# Microcontroller_board_Photodiode_plate.net
KiCad netlist of a schematic drawn in EasyEDA
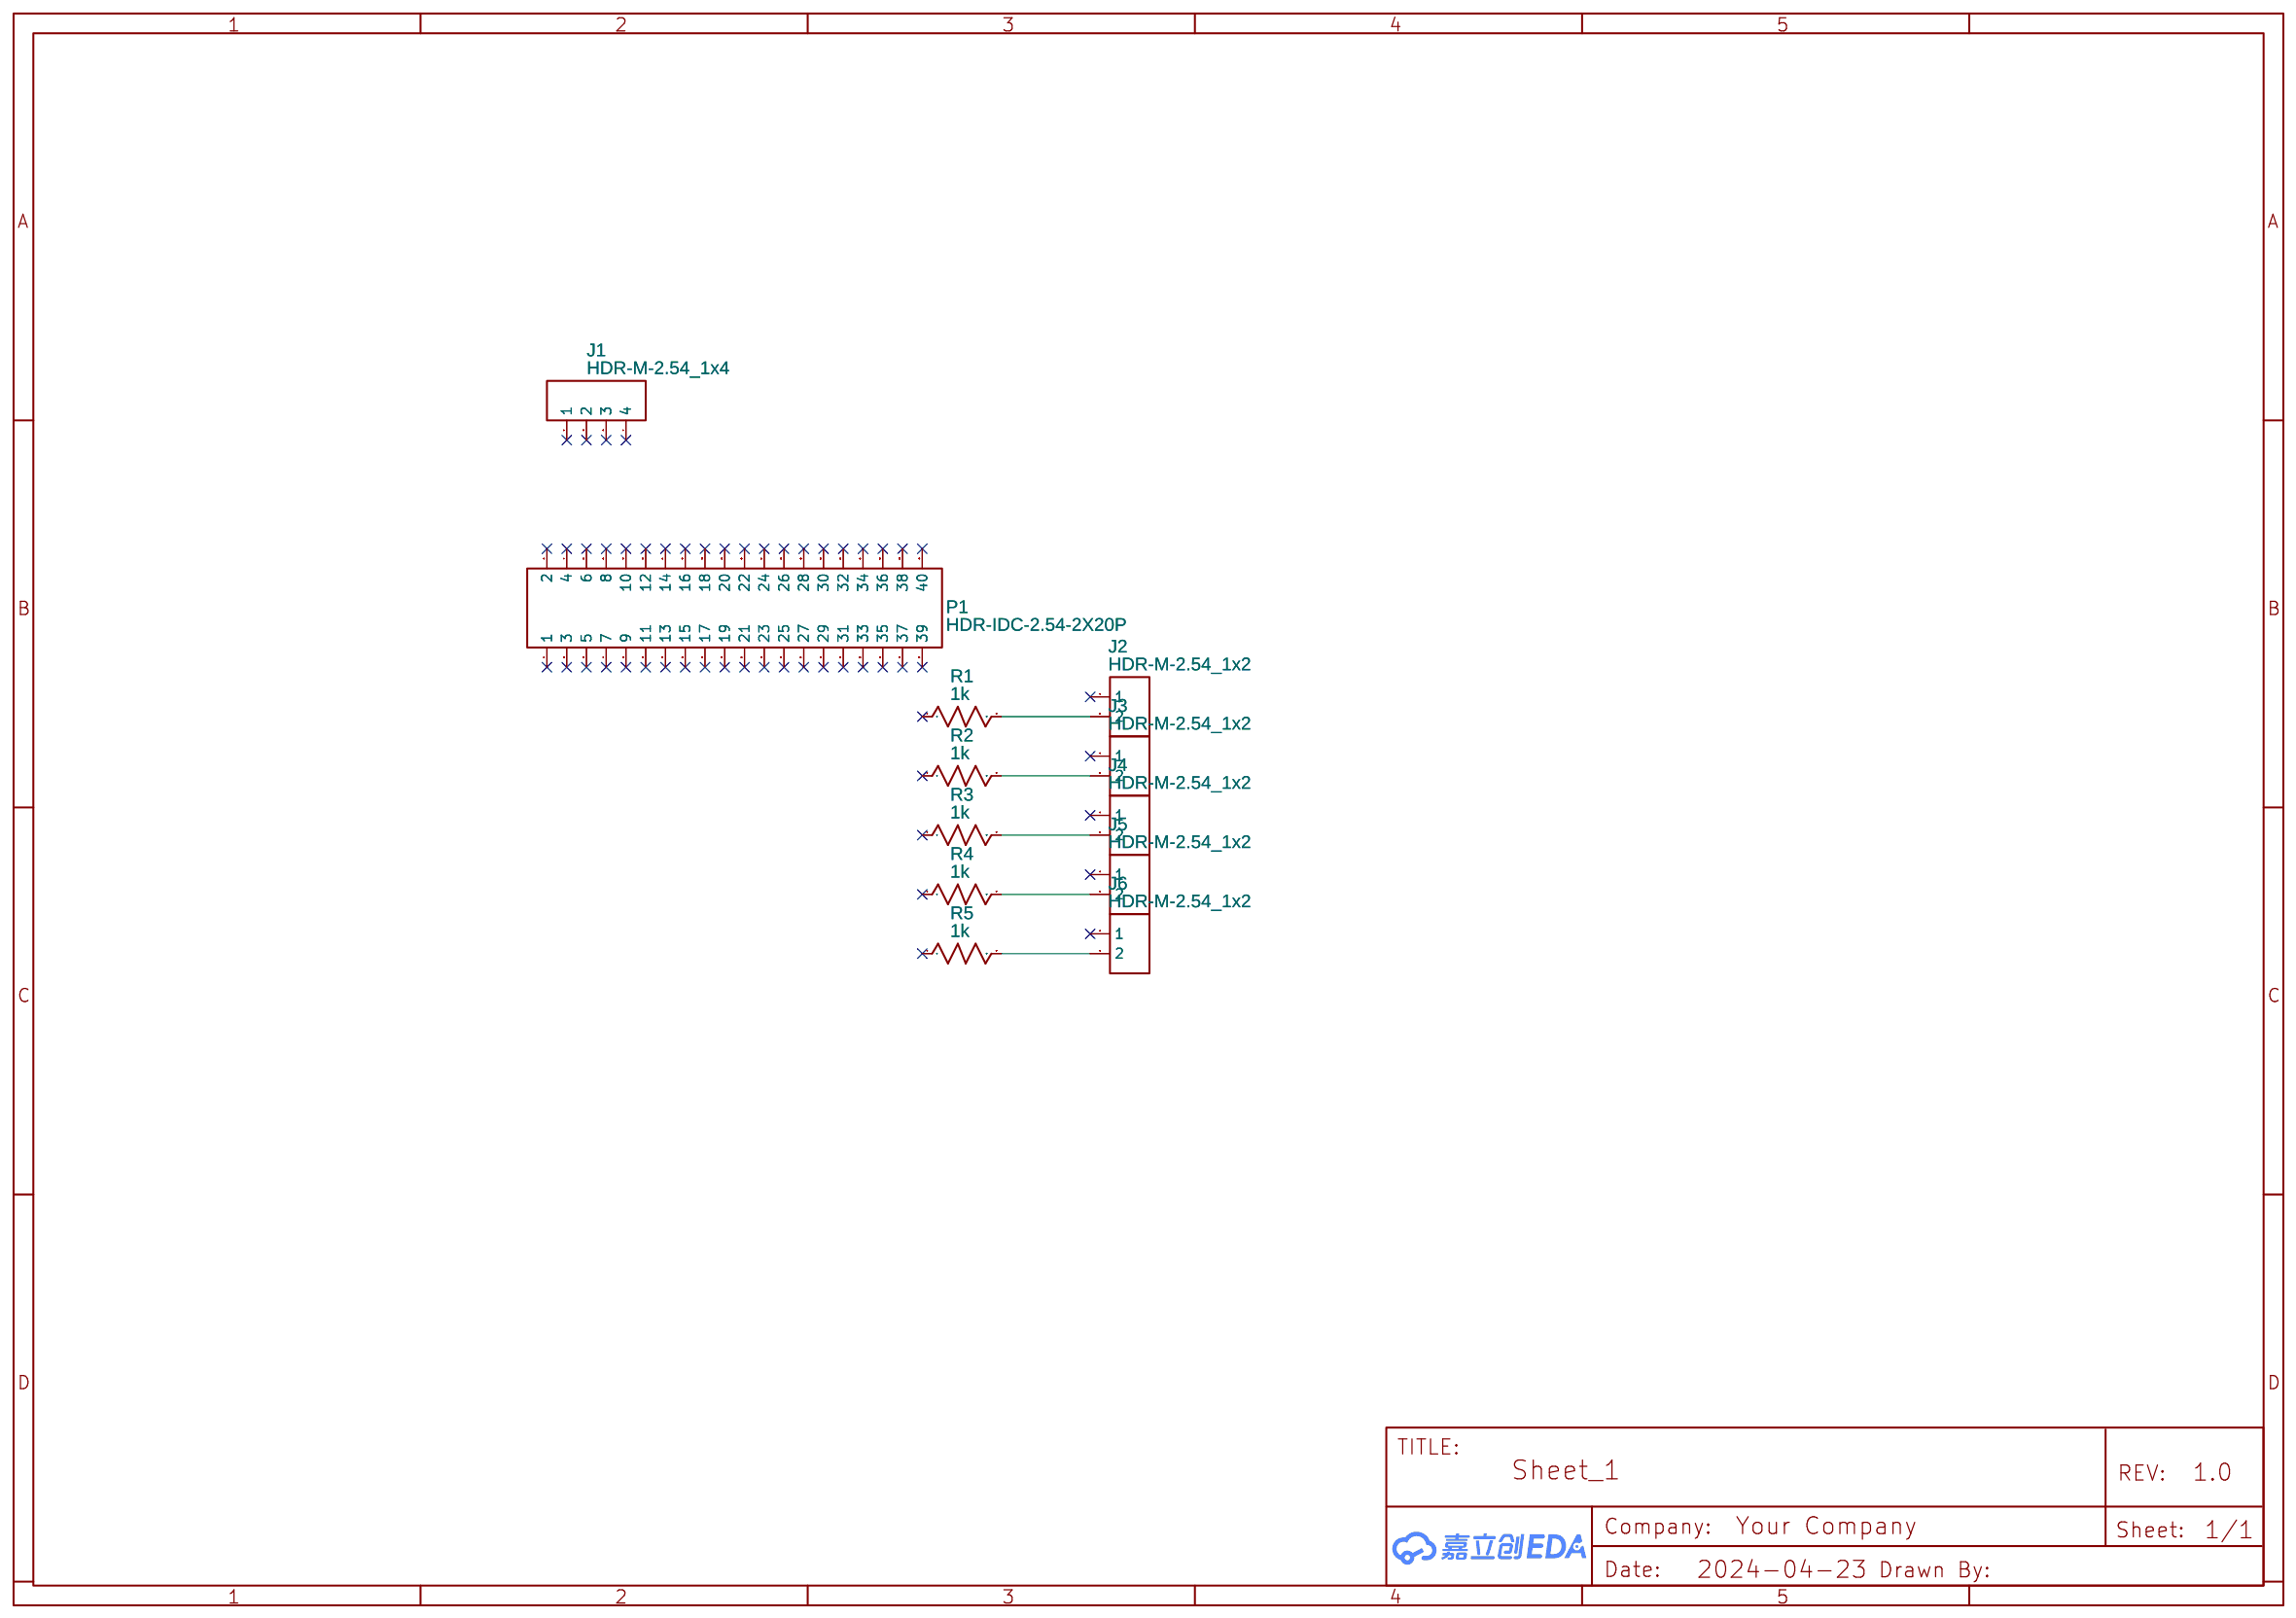
[diagram p0: schematic sheet]

(export (version "E")
  (design (tool "Eeschema 10.0.6"))
  (components
    (comp (ref "J1")
      (value "HDR-M-2.54_1x4")
      (fields (field (name "BOM_Supplier Part") "C124378"))
      (libsource (lib "") (part "HDR-M-2.54_1x4"))
    )
    (comp (ref "J2")
      (value "HDR-M-2.54_1x2")
      (fields (field (name "BOM_Supplier Part") "C124375"))
      (libsource (lib "") (part "HDR-M-2.54_1x2"))
    )
    (comp (ref "J3")
      (value "HDR-M-2.54_1x2")
      (fields (field (name "BOM_Supplier Part") "C124375"))
      (libsource (lib "") (part "HDR-M-2.54_1x2"))
    )
    (comp (ref "J4")
      (value "HDR-M-2.54_1x2")
      (fields (field (name "BOM_Supplier Part") "C124375"))
      (libsource (lib "") (part "HDR-M-2.54_1x2"))
    )
    (comp (ref "J5")
      (value "HDR-M-2.54_1x2")
      (fields (field (name "BOM_Supplier Part") "C124375"))
      (libsource (lib "") (part "HDR-M-2.54_1x2"))
    )
    (comp (ref "J6")
      (value "HDR-M-2.54_1x2")
      (fields (field (name "BOM_Supplier Part") "C124375"))
      (libsource (lib "") (part "HDR-M-2.54_1x2"))
    )
    (comp (ref "P1")
      (value "HDR-IDC-2.54-2X20P")
      (fields
        (field (name "BOM_Manufacturer Part") "IDC Box 2X20 2.54MM")
        (field (name "BOM_Supplier Part") "C9138")
      )
      (libsource (lib "") (part "HDR-IDC-2.54-2X20P"))
    )
    (comp (ref "R1") (value "1k") (libsource (lib "") (part "R_0603_US")))
    (comp (ref "R2") (value "1k") (libsource (lib "") (part "R_0603_US")))
    (comp (ref "R3") (value "1k") (libsource (lib "") (part "R_0603_US")))
    (comp (ref "R4") (value "1k") (libsource (lib "") (part "R_0603_US")))
    (comp (ref "R5") (value "1k") (libsource (lib "") (part "R_0603_US")))
  )
  (nets
    (net (code "1") (name "Net-(J2-Pad2)") (class "Default")
      (node (ref "J2") (pin "2") (pinfunction "2_2") (pintype "unspecified"))
      (node (ref "R1") (pin "2") (pinfunction "2_2") (pintype "unspecified"))
    )
    (net (code "2") (name "Net-(J3-Pad2)") (class "Default")
      (node (ref "J3") (pin "2") (pinfunction "2_2") (pintype "unspecified"))
      (node (ref "R2") (pin "2") (pinfunction "2_2") (pintype "unspecified"))
    )
    (net (code "3") (name "Net-(J4-Pad2)") (class "Default")
      (node (ref "J4") (pin "2") (pinfunction "2_2") (pintype "unspecified"))
      (node (ref "R3") (pin "2") (pinfunction "2_2") (pintype "unspecified"))
    )
    (net (code "4") (name "Net-(J5-Pad2)") (class "Default")
      (node (ref "J5") (pin "2") (pinfunction "2_2") (pintype "unspecified"))
      (node (ref "R4") (pin "2") (pinfunction "2_2") (pintype "unspecified"))
    )
    (net (code "5") (name "Net-(J6-Pad2)") (class "Default")
      (node (ref "J6") (pin "2") (pinfunction "2_2") (pintype "unspecified"))
      (node (ref "R5") (pin "2") (pinfunction "2_2") (pintype "unspecified"))
    )
    (net (code "6") (name "unconnected-(J1-Pad1)") (class "Default")
      (node (ref "J1") (pin "1") (pinfunction "1_1") (pintype "unspecified+no_connect"))
    )
    (net (code "7") (name "unconnected-(J1-Pad2)") (class "Default")
      (node (ref "J1") (pin "2") (pinfunction "2_2") (pintype "unspecified+no_connect"))
    )
    (net (code "8") (name "unconnected-(J1-Pad3)") (class "Default")
      (node (ref "J1") (pin "3") (pinfunction "3_3") (pintype "unspecified+no_connect"))
    )
    (net (code "9") (name "unconnected-(J1-Pad4)") (class "Default")
      (node (ref "J1") (pin "4") (pinfunction "4_4") (pintype "unspecified+no_connect"))
    )
    (net (code "10") (name "unconnected-(J2-Pad1)") (class "Default")
      (node (ref "J2") (pin "1") (pinfunction "1_1") (pintype "unspecified+no_connect"))
    )
    (net (code "11") (name "unconnected-(J3-Pad1)") (class "Default")
      (node (ref "J3") (pin "1") (pinfunction "1_1") (pintype "unspecified+no_connect"))
    )
    (net (code "12") (name "unconnected-(J4-Pad1)") (class "Default")
      (node (ref "J4") (pin "1") (pinfunction "1_1") (pintype "unspecified+no_connect"))
    )
    (net (code "13") (name "unconnected-(J5-Pad1)") (class "Default")
      (node (ref "J5") (pin "1") (pinfunction "1_1") (pintype "unspecified+no_connect"))
    )
    (net (code "14") (name "unconnected-(J6-Pad1)") (class "Default")
      (node (ref "J6") (pin "1") (pinfunction "1_1") (pintype "unspecified+no_connect"))
    )
    (net (code "15") (name "unconnected-(P1-Pad1)") (class "Default")
      (node (ref "P1") (pin "1") (pinfunction "1_1") (pintype "unspecified+no_connect"))
    )
    (net (code "16") (name "unconnected-(P1-Pad2)") (class "Default")
      (node (ref "P1") (pin "2") (pinfunction "2_2") (pintype "unspecified+no_connect"))
    )
    (net (code "17") (name "unconnected-(P1-Pad3)") (class "Default")
      (node (ref "P1") (pin "3") (pinfunction "3_3") (pintype "unspecified+no_connect"))
    )
    (net (code "18") (name "unconnected-(P1-Pad4)") (class "Default")
      (node (ref "P1") (pin "4") (pinfunction "4_4") (pintype "unspecified+no_connect"))
    )
    (net (code "19") (name "unconnected-(P1-Pad5)") (class "Default")
      (node (ref "P1") (pin "5") (pinfunction "5_5") (pintype "unspecified+no_connect"))
    )
    (net (code "20") (name "unconnected-(P1-Pad6)") (class "Default")
      (node (ref "P1") (pin "6") (pinfunction "6_6") (pintype "unspecified+no_connect"))
    )
    (net (code "21") (name "unconnected-(P1-Pad7)") (class "Default")
      (node (ref "P1") (pin "7") (pinfunction "7_7") (pintype "unspecified+no_connect"))
    )
    (net (code "22") (name "unconnected-(P1-Pad8)") (class "Default")
      (node (ref "P1") (pin "8") (pinfunction "8_8") (pintype "unspecified+no_connect"))
    )
    (net (code "23") (name "unconnected-(P1-Pad9)") (class "Default")
      (node (ref "P1") (pin "9") (pinfunction "9_9") (pintype "unspecified+no_connect"))
    )
    (net (code "24") (name "unconnected-(P1-Pad10)") (class "Default")
      (node (ref "P1") (pin "10") (pinfunction "10_10") (pintype "unspecified+no_connect"))
    )
    (net (code "25") (name "unconnected-(P1-Pad11)") (class "Default")
      (node (ref "P1") (pin "11") (pinfunction "11_11") (pintype "unspecified+no_connect"))
    )
    (net (code "26") (name "unconnected-(P1-Pad12)") (class "Default")
      (node (ref "P1") (pin "12") (pinfunction "12_12") (pintype "unspecified+no_connect"))
    )
    (net (code "27") (name "unconnected-(P1-Pad13)") (class "Default")
      (node (ref "P1") (pin "13") (pinfunction "13_13") (pintype "unspecified+no_connect"))
    )
    (net (code "28") (name "unconnected-(P1-Pad14)") (class "Default")
      (node (ref "P1") (pin "14") (pinfunction "14_14") (pintype "unspecified+no_connect"))
    )
    (net (code "29") (name "unconnected-(P1-Pad15)") (class "Default")
      (node (ref "P1") (pin "15") (pinfunction "15_15") (pintype "unspecified+no_connect"))
    )
    (net (code "30") (name "unconnected-(P1-Pad16)") (class "Default")
      (node (ref "P1") (pin "16") (pinfunction "16_16") (pintype "unspecified+no_connect"))
    )
    (net (code "31") (name "unconnected-(P1-Pad17)") (class "Default")
      (node (ref "P1") (pin "17") (pinfunction "17_17") (pintype "unspecified+no_connect"))
    )
    (net (code "32") (name "unconnected-(P1-Pad18)") (class "Default")
      (node (ref "P1") (pin "18") (pinfunction "18_18") (pintype "unspecified+no_connect"))
    )
    (net (code "33") (name "unconnected-(P1-Pad19)") (class "Default")
      (node (ref "P1") (pin "19") (pinfunction "19_19") (pintype "unspecified+no_connect"))
    )
    (net (code "34") (name "unconnected-(P1-Pad20)") (class "Default")
      (node (ref "P1") (pin "20") (pinfunction "20_20") (pintype "unspecified+no_connect"))
    )
    (net (code "35") (name "unconnected-(P1-Pad21)") (class "Default")
      (node (ref "P1") (pin "21") (pinfunction "21_21") (pintype "unspecified+no_connect"))
    )
    (net (code "36") (name "unconnected-(P1-Pad22)") (class "Default")
      (node (ref "P1") (pin "22") (pinfunction "22_22") (pintype "unspecified+no_connect"))
    )
    (net (code "37") (name "unconnected-(P1-Pad23)") (class "Default")
      (node (ref "P1") (pin "23") (pinfunction "23_23") (pintype "unspecified+no_connect"))
    )
    (net (code "38") (name "unconnected-(P1-Pad24)") (class "Default")
      (node (ref "P1") (pin "24") (pinfunction "24_24") (pintype "unspecified+no_connect"))
    )
    (net (code "39") (name "unconnected-(P1-Pad25)") (class "Default")
      (node (ref "P1") (pin "25") (pinfunction "25_25") (pintype "unspecified+no_connect"))
    )
    (net (code "40") (name "unconnected-(P1-Pad26)") (class "Default")
      (node (ref "P1") (pin "26") (pinfunction "26_26") (pintype "unspecified+no_connect"))
    )
    (net (code "41") (name "unconnected-(P1-Pad27)") (class "Default")
      (node (ref "P1") (pin "27") (pinfunction "27_27") (pintype "unspecified+no_connect"))
    )
    (net (code "42") (name "unconnected-(P1-Pad28)") (class "Default")
      (node (ref "P1") (pin "28") (pinfunction "28_28") (pintype "unspecified+no_connect"))
    )
    (net (code "43") (name "unconnected-(P1-Pad29)") (class "Default")
      (node (ref "P1") (pin "29") (pinfunction "29_29") (pintype "unspecified+no_connect"))
    )
    (net (code "44") (name "unconnected-(P1-Pad30)") (class "Default")
      (node (ref "P1") (pin "30") (pinfunction "30_30") (pintype "unspecified+no_connect"))
    )
    (net (code "45") (name "unconnected-(P1-Pad31)") (class "Default")
      (node (ref "P1") (pin "31") (pinfunction "31_31") (pintype "unspecified+no_connect"))
    )
    (net (code "46") (name "unconnected-(P1-Pad32)") (class "Default")
      (node (ref "P1") (pin "32") (pinfunction "32_32") (pintype "unspecified+no_connect"))
    )
    (net (code "47") (name "unconnected-(P1-Pad33)") (class "Default")
      (node (ref "P1") (pin "33") (pinfunction "33_33") (pintype "unspecified+no_connect"))
    )
    (net (code "48") (name "unconnected-(P1-Pad34)") (class "Default")
      (node (ref "P1") (pin "34") (pinfunction "34_34") (pintype "unspecified+no_connect"))
    )
    (net (code "49") (name "unconnected-(P1-Pad35)") (class "Default")
      (node (ref "P1") (pin "35") (pinfunction "35_35") (pintype "unspecified+no_connect"))
    )
    (net (code "50") (name "unconnected-(P1-Pad36)") (class "Default")
      (node (ref "P1") (pin "36") (pinfunction "36_36") (pintype "unspecified+no_connect"))
    )
    (net (code "51") (name "unconnected-(P1-Pad37)") (class "Default")
      (node (ref "P1") (pin "37") (pinfunction "37_37") (pintype "unspecified+no_connect"))
    )
    (net (code "52") (name "unconnected-(P1-Pad38)") (class "Default")
      (node (ref "P1") (pin "38") (pinfunction "38_38") (pintype "unspecified+no_connect"))
    )
    (net (code "53") (name "unconnected-(P1-Pad39)") (class "Default")
      (node (ref "P1") (pin "39") (pinfunction "39_39") (pintype "unspecified+no_connect"))
    )
    (net (code "54") (name "unconnected-(P1-Pad40)") (class "Default")
      (node (ref "P1") (pin "40") (pinfunction "40_40") (pintype "unspecified+no_connect"))
    )
    (net (code "55") (name "unconnected-(R1-Pad1)") (class "Default")
      (node (ref "R1") (pin "1") (pinfunction "1_1") (pintype "unspecified+no_connect"))
    )
    (net (code "56") (name "unconnected-(R2-Pad1)") (class "Default")
      (node (ref "R2") (pin "1") (pinfunction "1_1") (pintype "unspecified+no_connect"))
    )
    (net (code "57") (name "unconnected-(R3-Pad1)") (class "Default")
      (node (ref "R3") (pin "1") (pinfunction "1_1") (pintype "unspecified+no_connect"))
    )
    (net (code "58") (name "unconnected-(R4-Pad1)") (class "Default")
      (node (ref "R4") (pin "1") (pinfunction "1_1") (pintype "unspecified+no_connect"))
    )
    (net (code "59") (name "unconnected-(R5-Pad1)") (class "Default")
      (node (ref "R5") (pin "1") (pinfunction "1_1") (pintype "unspecified+no_connect"))
    )
  )
)
